# STM32F4_TFT-Proto_Adapter_FSMC_Vertical.net
KiCad netlist of a schematic drawn in EAGLE
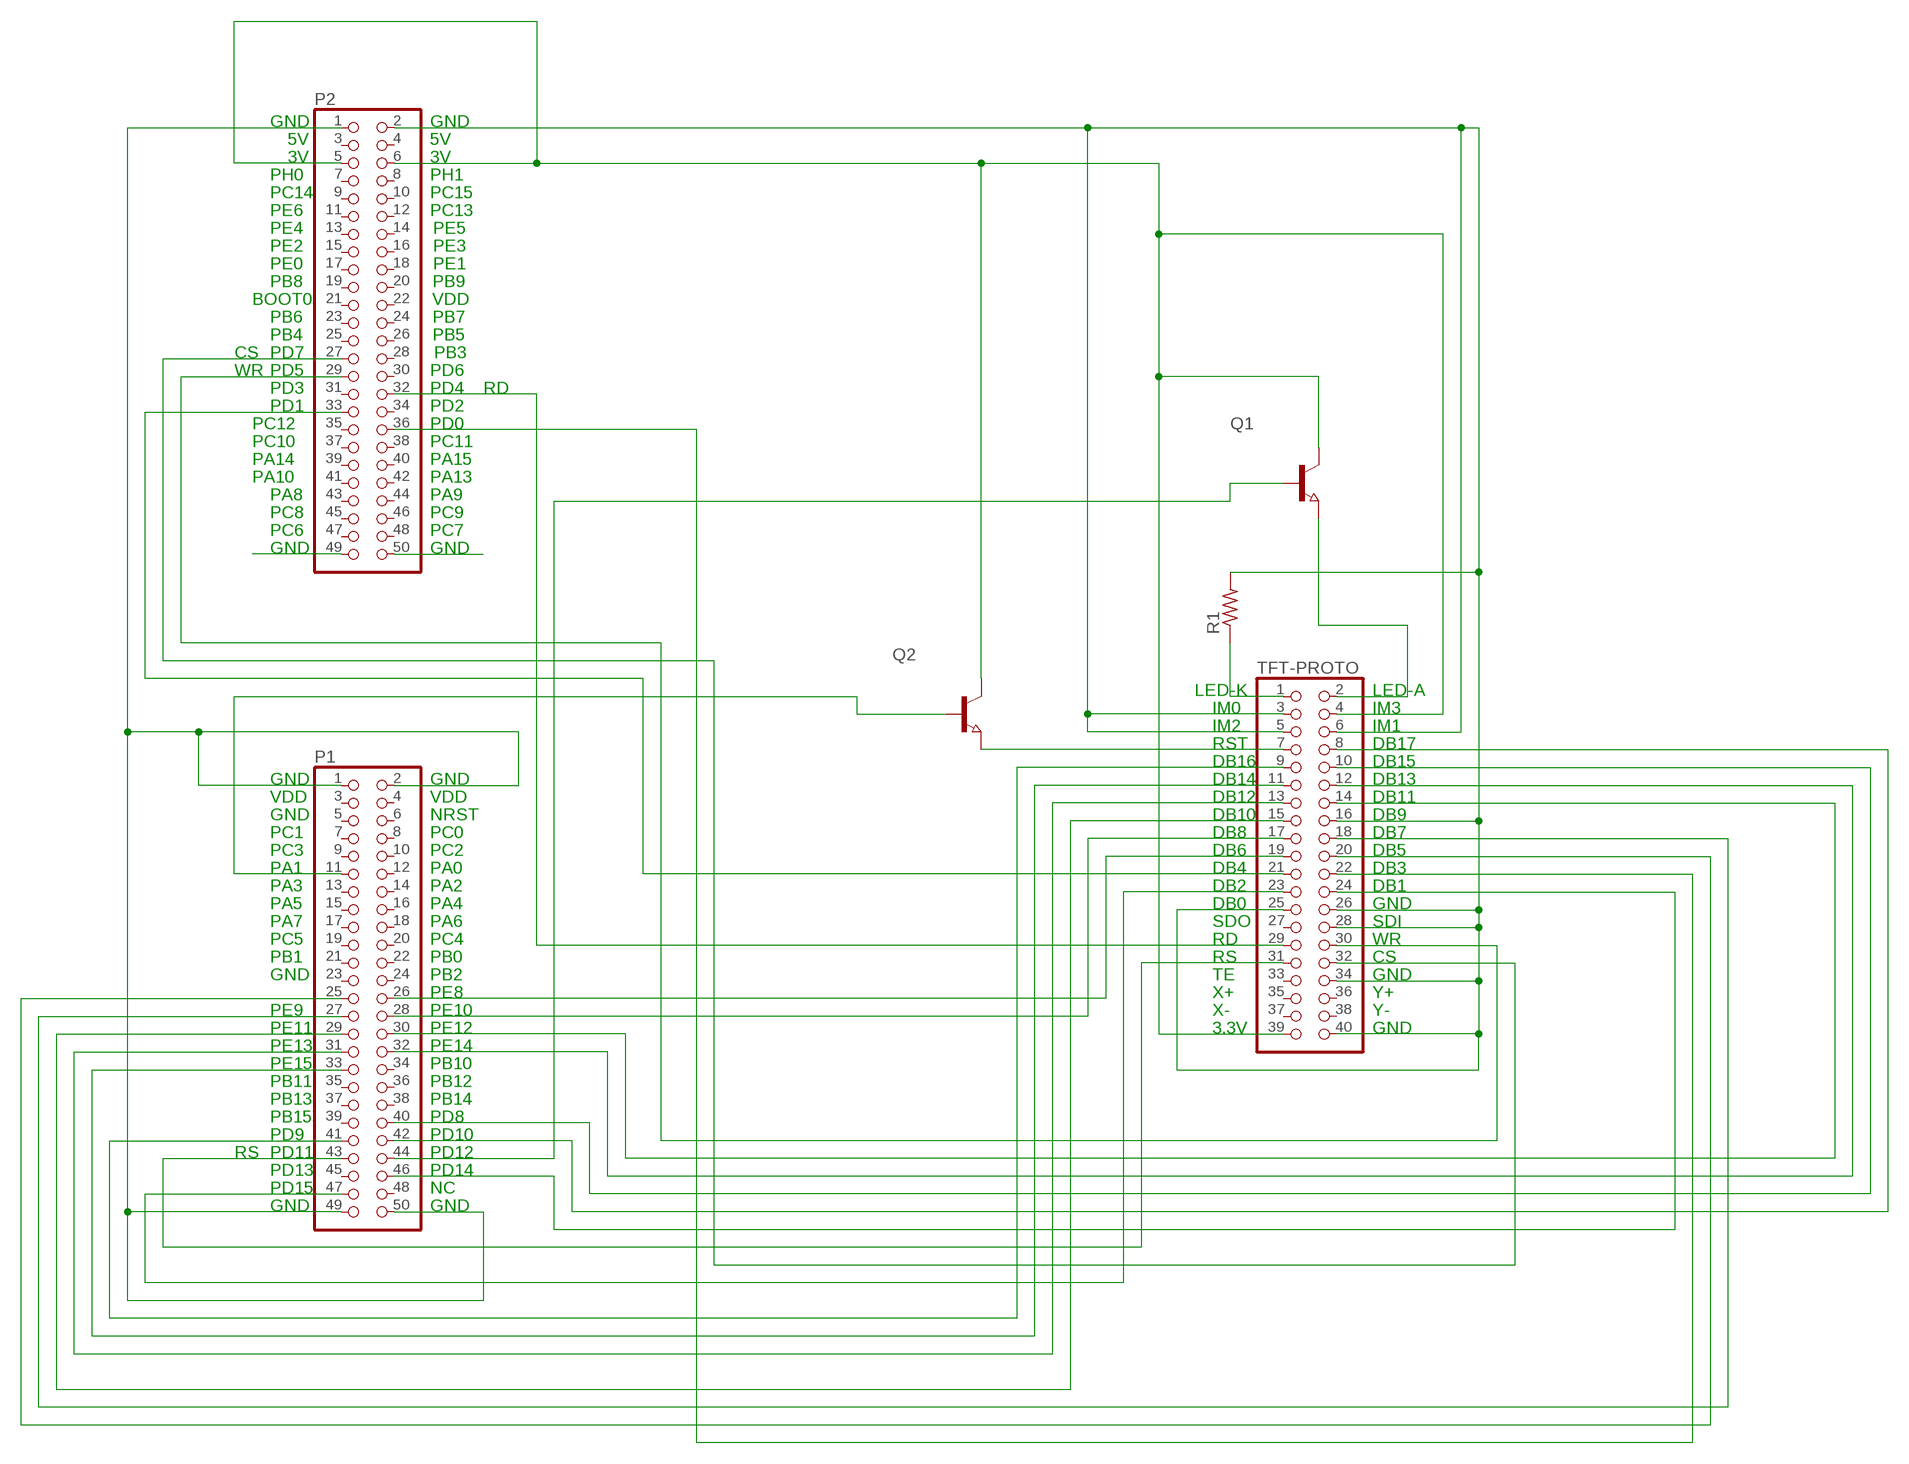
[diagram p0: schematic, sheet 1]

(export (version "E")
  (design (tool "Eeschema 10.0.6"))
  (components
    (comp (ref "P1")
      (value "PINHD-2X25")
      (footprint "eagle-import:2X25")
      (libsource (lib "eagle-import") (part "PINHD-2X25"))
    )
    (comp (ref "P2")
      (value "PINHD-2X25")
      (footprint "eagle-import:2X25")
      (libsource (lib "eagle-import") (part "PINHD-2X25"))
    )
    (comp (ref "Q1")
      (value "NPN-TRANSISTOR_SOT23")
      (footprint "eagle-import:SOT23")
      (libsource (lib "eagle-import") (part "NPN-TRANSISTOR_SOT23"))
    )
    (comp (ref "Q2")
      (value "NPN-TRANSISTOR_SOT23")
      (footprint "eagle-import:SOT23")
      (libsource (lib "eagle-import") (part "NPN-TRANSISTOR_SOT23"))
    )
    (comp (ref "R1")
      (value "R-US_R0805")
      (footprint "eagle-import:R0805")
      (libsource (lib "eagle-import") (part "R-US_R0805"))
    )
    (comp (ref "TFT-PROTO")
      (value "PINHD-2X20")
      (footprint "eagle-import:2X20")
      (libsource (lib "eagle-import") (part "PINHD-2X20"))
    )
  )
  (nets
    (net (code "1") (name "/GND") (class "Default")
      (node (ref "P1") (pin "1") (pinfunction "1_1") (pintype "passive"))
      (node (ref "P1") (pin "2") (pinfunction "2_2") (pintype "passive"))
      (node (ref "P1") (pin "49") (pinfunction "49_49") (pintype "passive"))
      (node (ref "P1") (pin "50") (pinfunction "50_50") (pintype "passive"))
      (node (ref "P2") (pin "1") (pinfunction "1_1") (pintype "passive"))
      (node (ref "P2") (pin "2") (pinfunction "2_2") (pintype "passive"))
      (node (ref "P2") (pin "49") (pinfunction "49_49") (pintype "passive"))
      (node (ref "P2") (pin "50") (pinfunction "50_50") (pintype "passive"))
      (node (ref "R1") (pin "2") (pinfunction "2_2") (pintype "passive"))
      (node (ref "TFT-PROTO") (pin "16") (pinfunction "16_16") (pintype "passive"))
      (node (ref "TFT-PROTO") (pin "25") (pinfunction "25_25") (pintype "passive"))
      (node (ref "TFT-PROTO") (pin "26") (pinfunction "26_26") (pintype "passive"))
      (node (ref "TFT-PROTO") (pin "28") (pinfunction "28_28") (pintype "passive"))
      (node (ref "TFT-PROTO") (pin "3") (pinfunction "3_3") (pintype "passive"))
      (node (ref "TFT-PROTO") (pin "34") (pinfunction "34_34") (pintype "passive"))
      (node (ref "TFT-PROTO") (pin "40") (pinfunction "40_40") (pintype "passive"))
      (node (ref "TFT-PROTO") (pin "5") (pinfunction "5_5") (pintype "passive"))
      (node (ref "TFT-PROTO") (pin "6") (pinfunction "6_6") (pintype "passive"))
    )
    (net (code "2") (name "Net-(P1-Pad25)") (class "Default")
      (node (ref "P1") (pin "25") (pinfunction "25_25") (pintype "passive"))
      (node (ref "TFT-PROTO") (pin "20") (pinfunction "20_20") (pintype "passive"))
    )
    (net (code "3") (name "Net-(P1-Pad26)") (class "Default")
      (node (ref "P1") (pin "26") (pinfunction "26_26") (pintype "passive"))
      (node (ref "TFT-PROTO") (pin "19") (pinfunction "19_19") (pintype "passive"))
    )
    (net (code "4") (name "Net-(P1-Pad27)") (class "Default")
      (node (ref "P1") (pin "27") (pinfunction "27_27") (pintype "passive"))
      (node (ref "TFT-PROTO") (pin "18") (pinfunction "18_18") (pintype "passive"))
    )
    (net (code "5") (name "Net-(P1-Pad28)") (class "Default")
      (node (ref "P1") (pin "28") (pinfunction "28_28") (pintype "passive"))
      (node (ref "TFT-PROTO") (pin "17") (pinfunction "17_17") (pintype "passive"))
    )
    (net (code "6") (name "Net-(P1-Pad29)") (class "Default")
      (node (ref "P1") (pin "29") (pinfunction "29_29") (pintype "passive"))
      (node (ref "TFT-PROTO") (pin "15") (pinfunction "15_15") (pintype "passive"))
    )
    (net (code "7") (name "Net-(P1-Pad30)") (class "Default")
      (node (ref "P1") (pin "30") (pinfunction "30_30") (pintype "passive"))
      (node (ref "TFT-PROTO") (pin "14") (pinfunction "14_14") (pintype "passive"))
    )
    (net (code "8") (name "Net-(P1-Pad31)") (class "Default")
      (node (ref "P1") (pin "31") (pinfunction "31_31") (pintype "passive"))
      (node (ref "TFT-PROTO") (pin "13") (pinfunction "13_13") (pintype "passive"))
    )
    (net (code "9") (name "Net-(P1-Pad32)") (class "Default")
      (node (ref "P1") (pin "32") (pinfunction "32_32") (pintype "passive"))
      (node (ref "TFT-PROTO") (pin "12") (pinfunction "12_12") (pintype "passive"))
    )
    (net (code "10") (name "Net-(P1-Pad33)") (class "Default")
      (node (ref "P1") (pin "33") (pinfunction "33_33") (pintype "passive"))
      (node (ref "TFT-PROTO") (pin "11") (pinfunction "11_11") (pintype "passive"))
    )
    (net (code "11") (name "Net-(P1-Pad40)") (class "Default")
      (node (ref "P1") (pin "40") (pinfunction "40_40") (pintype "passive"))
      (node (ref "TFT-PROTO") (pin "10") (pinfunction "10_10") (pintype "passive"))
    )
    (net (code "12") (name "Net-(P1-Pad41)") (class "Default")
      (node (ref "P1") (pin "41") (pinfunction "41_41") (pintype "passive"))
      (node (ref "TFT-PROTO") (pin "9") (pinfunction "9_9") (pintype "passive"))
    )
    (net (code "13") (name "Net-(P1-Pad42)") (class "Default")
      (node (ref "P1") (pin "42") (pinfunction "42_42") (pintype "passive"))
      (node (ref "TFT-PROTO") (pin "8") (pinfunction "8_8") (pintype "passive"))
    )
    (net (code "14") (name "Net-(P1-Pad43)") (class "Default")
      (node (ref "P1") (pin "43") (pinfunction "43_43") (pintype "passive"))
      (node (ref "TFT-PROTO") (pin "31") (pinfunction "31_31") (pintype "passive"))
    )
    (net (code "15") (name "Net-(P1-Pad46)") (class "Default")
      (node (ref "P1") (pin "46") (pinfunction "46_46") (pintype "passive"))
      (node (ref "TFT-PROTO") (pin "24") (pinfunction "24_24") (pintype "passive"))
    )
    (net (code "16") (name "Net-(P1-Pad47)") (class "Default")
      (node (ref "P1") (pin "47") (pinfunction "47_47") (pintype "passive"))
      (node (ref "TFT-PROTO") (pin "23") (pinfunction "23_23") (pintype "passive"))
    )
    (net (code "17") (name "Net-(P2-Pad27)") (class "Default")
      (node (ref "P2") (pin "27") (pinfunction "27_27") (pintype "passive"))
      (node (ref "TFT-PROTO") (pin "32") (pinfunction "32_32") (pintype "passive"))
    )
    (net (code "18") (name "Net-(P2-Pad29)") (class "Default")
      (node (ref "P2") (pin "29") (pinfunction "29_29") (pintype "passive"))
      (node (ref "TFT-PROTO") (pin "30") (pinfunction "30_30") (pintype "passive"))
    )
    (net (code "19") (name "Net-(P2-Pad32)") (class "Default")
      (node (ref "P2") (pin "32") (pinfunction "32_32") (pintype "passive"))
      (node (ref "TFT-PROTO") (pin "29") (pinfunction "29_29") (pintype "passive"))
    )
    (net (code "20") (name "Net-(P2-Pad33)") (class "Default")
      (node (ref "P2") (pin "33") (pinfunction "33_33") (pintype "passive"))
      (node (ref "TFT-PROTO") (pin "21") (pinfunction "21_21") (pintype "passive"))
    )
    (net (code "21") (name "Net-(P2-Pad36)") (class "Default")
      (node (ref "P2") (pin "36") (pinfunction "36_36") (pintype "passive"))
      (node (ref "TFT-PROTO") (pin "22") (pinfunction "22_22") (pintype "passive"))
    )
    (net (code "22") (name "Net-(Q1-B)") (class "Default")
      (node (ref "P1") (pin "44") (pinfunction "44_44") (pintype "passive"))
      (node (ref "Q1") (pin "1") (pinfunction "B_1") (pintype "passive"))
    )
    (net (code "23") (name "Net-(Q1-C)") (class "Default")
      (node (ref "P2") (pin "5") (pinfunction "5_5") (pintype "passive"))
      (node (ref "P2") (pin "6") (pinfunction "6_6") (pintype "passive"))
      (node (ref "Q1") (pin "3") (pinfunction "C_3") (pintype "passive"))
      (node (ref "Q2") (pin "3") (pinfunction "C_3") (pintype "passive"))
      (node (ref "TFT-PROTO") (pin "39") (pinfunction "39_39") (pintype "passive"))
      (node (ref "TFT-PROTO") (pin "4") (pinfunction "4_4") (pintype "passive"))
    )
    (net (code "24") (name "Net-(Q1-E)") (class "Default")
      (node (ref "Q1") (pin "2") (pinfunction "E_2") (pintype "passive"))
      (node (ref "TFT-PROTO") (pin "2") (pinfunction "2_2") (pintype "passive"))
    )
    (net (code "25") (name "Net-(Q2-B)") (class "Default")
      (node (ref "P1") (pin "11") (pinfunction "11_11") (pintype "passive"))
      (node (ref "Q2") (pin "1") (pinfunction "B_1") (pintype "passive"))
    )
    (net (code "26") (name "Net-(Q2-E)") (class "Default")
      (node (ref "Q2") (pin "2") (pinfunction "E_2") (pintype "passive"))
      (node (ref "TFT-PROTO") (pin "7") (pinfunction "7_7") (pintype "passive"))
    )
    (net (code "27") (name "Net-(R1-Pad1)") (class "Default")
      (node (ref "R1") (pin "1") (pinfunction "1_1") (pintype "passive"))
      (node (ref "TFT-PROTO") (pin "1") (pinfunction "1_1") (pintype "passive"))
    )
    (net (code "28") (name "unconnected-(P1-Pad3)") (class "Default")
      (node (ref "P1") (pin "3") (pinfunction "3_3") (pintype "passive"))
    )
    (net (code "29") (name "unconnected-(P1-Pad4)") (class "Default")
      (node (ref "P1") (pin "4") (pinfunction "4_4") (pintype "passive"))
    )
    (net (code "30") (name "unconnected-(P1-Pad5)") (class "Default")
      (node (ref "P1") (pin "5") (pinfunction "5_5") (pintype "passive"))
    )
    (net (code "31") (name "unconnected-(P1-Pad6)") (class "Default")
      (node (ref "P1") (pin "6") (pinfunction "6_6") (pintype "passive"))
    )
    (net (code "32") (name "unconnected-(P1-Pad7)") (class "Default")
      (node (ref "P1") (pin "7") (pinfunction "7_7") (pintype "passive"))
    )
    (net (code "33") (name "unconnected-(P1-Pad8)") (class "Default")
      (node (ref "P1") (pin "8") (pinfunction "8_8") (pintype "passive"))
    )
    (net (code "34") (name "unconnected-(P1-Pad9)") (class "Default")
      (node (ref "P1") (pin "9") (pinfunction "9_9") (pintype "passive"))
    )
    (net (code "35") (name "unconnected-(P1-Pad10)") (class "Default")
      (node (ref "P1") (pin "10") (pinfunction "10_10") (pintype "passive"))
    )
    (net (code "36") (name "unconnected-(P1-Pad12)") (class "Default")
      (node (ref "P1") (pin "12") (pinfunction "12_12") (pintype "passive"))
    )
    (net (code "37") (name "unconnected-(P1-Pad13)") (class "Default")
      (node (ref "P1") (pin "13") (pinfunction "13_13") (pintype "passive"))
    )
    (net (code "38") (name "unconnected-(P1-Pad14)") (class "Default")
      (node (ref "P1") (pin "14") (pinfunction "14_14") (pintype "passive"))
    )
    (net (code "39") (name "unconnected-(P1-Pad15)") (class "Default")
      (node (ref "P1") (pin "15") (pinfunction "15_15") (pintype "passive"))
    )
    (net (code "40") (name "unconnected-(P1-Pad16)") (class "Default")
      (node (ref "P1") (pin "16") (pinfunction "16_16") (pintype "passive"))
    )
    (net (code "41") (name "unconnected-(P1-Pad17)") (class "Default")
      (node (ref "P1") (pin "17") (pinfunction "17_17") (pintype "passive"))
    )
    (net (code "42") (name "unconnected-(P1-Pad18)") (class "Default")
      (node (ref "P1") (pin "18") (pinfunction "18_18") (pintype "passive"))
    )
    (net (code "43") (name "unconnected-(P1-Pad19)") (class "Default")
      (node (ref "P1") (pin "19") (pinfunction "19_19") (pintype "passive"))
    )
    (net (code "44") (name "unconnected-(P1-Pad20)") (class "Default")
      (node (ref "P1") (pin "20") (pinfunction "20_20") (pintype "passive"))
    )
    (net (code "45") (name "unconnected-(P1-Pad21)") (class "Default")
      (node (ref "P1") (pin "21") (pinfunction "21_21") (pintype "passive"))
    )
    (net (code "46") (name "unconnected-(P1-Pad22)") (class "Default")
      (node (ref "P1") (pin "22") (pinfunction "22_22") (pintype "passive"))
    )
    (net (code "47") (name "unconnected-(P1-Pad23)") (class "Default")
      (node (ref "P1") (pin "23") (pinfunction "23_23") (pintype "passive"))
    )
    (net (code "48") (name "unconnected-(P1-Pad24)") (class "Default")
      (node (ref "P1") (pin "24") (pinfunction "24_24") (pintype "passive"))
    )
    (net (code "49") (name "unconnected-(P1-Pad34)") (class "Default")
      (node (ref "P1") (pin "34") (pinfunction "34_34") (pintype "passive"))
    )
    (net (code "50") (name "unconnected-(P1-Pad35)") (class "Default")
      (node (ref "P1") (pin "35") (pinfunction "35_35") (pintype "passive"))
    )
    (net (code "51") (name "unconnected-(P1-Pad36)") (class "Default")
      (node (ref "P1") (pin "36") (pinfunction "36_36") (pintype "passive"))
    )
    (net (code "52") (name "unconnected-(P1-Pad37)") (class "Default")
      (node (ref "P1") (pin "37") (pinfunction "37_37") (pintype "passive"))
    )
    (net (code "53") (name "unconnected-(P1-Pad38)") (class "Default")
      (node (ref "P1") (pin "38") (pinfunction "38_38") (pintype "passive"))
    )
    (net (code "54") (name "unconnected-(P1-Pad39)") (class "Default")
      (node (ref "P1") (pin "39") (pinfunction "39_39") (pintype "passive"))
    )
    (net (code "55") (name "unconnected-(P1-Pad45)") (class "Default")
      (node (ref "P1") (pin "45") (pinfunction "45_45") (pintype "passive"))
    )
    (net (code "56") (name "unconnected-(P1-Pad48)") (class "Default")
      (node (ref "P1") (pin "48") (pinfunction "48_48") (pintype "passive"))
    )
    (net (code "57") (name "unconnected-(P2-Pad3)") (class "Default")
      (node (ref "P2") (pin "3") (pinfunction "3_3") (pintype "passive"))
    )
    (net (code "58") (name "unconnected-(P2-Pad4)") (class "Default")
      (node (ref "P2") (pin "4") (pinfunction "4_4") (pintype "passive"))
    )
    (net (code "59") (name "unconnected-(P2-Pad7)") (class "Default")
      (node (ref "P2") (pin "7") (pinfunction "7_7") (pintype "passive"))
    )
    (net (code "60") (name "unconnected-(P2-Pad8)") (class "Default")
      (node (ref "P2") (pin "8") (pinfunction "8_8") (pintype "passive"))
    )
    (net (code "61") (name "unconnected-(P2-Pad9)") (class "Default")
      (node (ref "P2") (pin "9") (pinfunction "9_9") (pintype "passive"))
    )
    (net (code "62") (name "unconnected-(P2-Pad10)") (class "Default")
      (node (ref "P2") (pin "10") (pinfunction "10_10") (pintype "passive"))
    )
    (net (code "63") (name "unconnected-(P2-Pad11)") (class "Default")
      (node (ref "P2") (pin "11") (pinfunction "11_11") (pintype "passive"))
    )
    (net (code "64") (name "unconnected-(P2-Pad12)") (class "Default")
      (node (ref "P2") (pin "12") (pinfunction "12_12") (pintype "passive"))
    )
    (net (code "65") (name "unconnected-(P2-Pad13)") (class "Default")
      (node (ref "P2") (pin "13") (pinfunction "13_13") (pintype "passive"))
    )
    (net (code "66") (name "unconnected-(P2-Pad14)") (class "Default")
      (node (ref "P2") (pin "14") (pinfunction "14_14") (pintype "passive"))
    )
    (net (code "67") (name "unconnected-(P2-Pad15)") (class "Default")
      (node (ref "P2") (pin "15") (pinfunction "15_15") (pintype "passive"))
    )
    (net (code "68") (name "unconnected-(P2-Pad16)") (class "Default")
      (node (ref "P2") (pin "16") (pinfunction "16_16") (pintype "passive"))
    )
    (net (code "69") (name "unconnected-(P2-Pad17)") (class "Default")
      (node (ref "P2") (pin "17") (pinfunction "17_17") (pintype "passive"))
    )
    (net (code "70") (name "unconnected-(P2-Pad18)") (class "Default")
      (node (ref "P2") (pin "18") (pinfunction "18_18") (pintype "passive"))
    )
    (net (code "71") (name "unconnected-(P2-Pad19)") (class "Default")
      (node (ref "P2") (pin "19") (pinfunction "19_19") (pintype "passive"))
    )
    (net (code "72") (name "unconnected-(P2-Pad20)") (class "Default")
      (node (ref "P2") (pin "20") (pinfunction "20_20") (pintype "passive"))
    )
    (net (code "73") (name "unconnected-(P2-Pad21)") (class "Default")
      (node (ref "P2") (pin "21") (pinfunction "21_21") (pintype "passive"))
    )
    (net (code "74") (name "unconnected-(P2-Pad22)") (class "Default")
      (node (ref "P2") (pin "22") (pinfunction "22_22") (pintype "passive"))
    )
    (net (code "75") (name "unconnected-(P2-Pad23)") (class "Default")
      (node (ref "P2") (pin "23") (pinfunction "23_23") (pintype "passive"))
    )
    (net (code "76") (name "unconnected-(P2-Pad24)") (class "Default")
      (node (ref "P2") (pin "24") (pinfunction "24_24") (pintype "passive"))
    )
    (net (code "77") (name "unconnected-(P2-Pad25)") (class "Default")
      (node (ref "P2") (pin "25") (pinfunction "25_25") (pintype "passive"))
    )
    (net (code "78") (name "unconnected-(P2-Pad26)") (class "Default")
      (node (ref "P2") (pin "26") (pinfunction "26_26") (pintype "passive"))
    )
    (net (code "79") (name "unconnected-(P2-Pad28)") (class "Default")
      (node (ref "P2") (pin "28") (pinfunction "28_28") (pintype "passive"))
    )
    (net (code "80") (name "unconnected-(P2-Pad30)") (class "Default")
      (node (ref "P2") (pin "30") (pinfunction "30_30") (pintype "passive"))
    )
    (net (code "81") (name "unconnected-(P2-Pad31)") (class "Default")
      (node (ref "P2") (pin "31") (pinfunction "31_31") (pintype "passive"))
    )
    (net (code "82") (name "unconnected-(P2-Pad34)") (class "Default")
      (node (ref "P2") (pin "34") (pinfunction "34_34") (pintype "passive"))
    )
    (net (code "83") (name "unconnected-(P2-Pad35)") (class "Default")
      (node (ref "P2") (pin "35") (pinfunction "35_35") (pintype "passive"))
    )
    (net (code "84") (name "unconnected-(P2-Pad37)") (class "Default")
      (node (ref "P2") (pin "37") (pinfunction "37_37") (pintype "passive"))
    )
    (net (code "85") (name "unconnected-(P2-Pad38)") (class "Default")
      (node (ref "P2") (pin "38") (pinfunction "38_38") (pintype "passive"))
    )
    (net (code "86") (name "unconnected-(P2-Pad39)") (class "Default")
      (node (ref "P2") (pin "39") (pinfunction "39_39") (pintype "passive"))
    )
    (net (code "87") (name "unconnected-(P2-Pad40)") (class "Default")
      (node (ref "P2") (pin "40") (pinfunction "40_40") (pintype "passive"))
    )
    (net (code "88") (name "unconnected-(P2-Pad41)") (class "Default")
      (node (ref "P2") (pin "41") (pinfunction "41_41") (pintype "passive"))
    )
    (net (code "89") (name "unconnected-(P2-Pad42)") (class "Default")
      (node (ref "P2") (pin "42") (pinfunction "42_42") (pintype "passive"))
    )
    (net (code "90") (name "unconnected-(P2-Pad43)") (class "Default")
      (node (ref "P2") (pin "43") (pinfunction "43_43") (pintype "passive"))
    )
    (net (code "91") (name "unconnected-(P2-Pad44)") (class "Default")
      (node (ref "P2") (pin "44") (pinfunction "44_44") (pintype "passive"))
    )
    (net (code "92") (name "unconnected-(P2-Pad45)") (class "Default")
      (node (ref "P2") (pin "45") (pinfunction "45_45") (pintype "passive"))
    )
    (net (code "93") (name "unconnected-(P2-Pad46)") (class "Default")
      (node (ref "P2") (pin "46") (pinfunction "46_46") (pintype "passive"))
    )
    (net (code "94") (name "unconnected-(P2-Pad47)") (class "Default")
      (node (ref "P2") (pin "47") (pinfunction "47_47") (pintype "passive"))
    )
    (net (code "95") (name "unconnected-(P2-Pad48)") (class "Default")
      (node (ref "P2") (pin "48") (pinfunction "48_48") (pintype "passive"))
    )
    (net (code "96") (name "unconnected-(TFT-PROTO-Pad27)") (class "Default")
      (node (ref "TFT-PROTO") (pin "27") (pinfunction "27_27") (pintype "passive"))
    )
    (net (code "97") (name "unconnected-(TFT-PROTO-Pad33)") (class "Default")
      (node (ref "TFT-PROTO") (pin "33") (pinfunction "33_33") (pintype "passive"))
    )
    (net (code "98") (name "unconnected-(TFT-PROTO-Pad35)") (class "Default")
      (node (ref "TFT-PROTO") (pin "35") (pinfunction "35_35") (pintype "passive"))
    )
    (net (code "99") (name "unconnected-(TFT-PROTO-Pad36)") (class "Default")
      (node (ref "TFT-PROTO") (pin "36") (pinfunction "36_36") (pintype "passive"))
    )
    (net (code "100") (name "unconnected-(TFT-PROTO-Pad37)") (class "Default")
      (node (ref "TFT-PROTO") (pin "37") (pinfunction "37_37") (pintype "passive"))
    )
    (net (code "101") (name "unconnected-(TFT-PROTO-Pad38)") (class "Default")
      (node (ref "TFT-PROTO") (pin "38") (pinfunction "38_38") (pintype "passive"))
    )
  )
)
